# 5v_power_supply.net
KiCad netlist of a schematic drawn in EAGLE
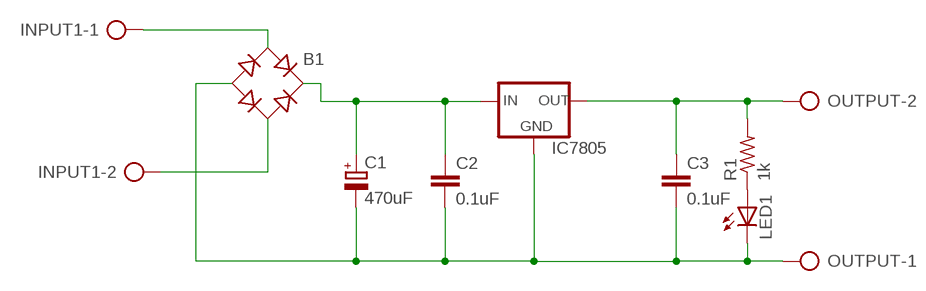
[diagram p0: schematic, sheet 1]

(export (version "E")
  (design (tool "Eeschema 10.0.6"))
  (components
    (comp (ref "B1")
      (value "RB1A")
      (footprint "eagle-import:RB1A")
      (libsource (lib "eagle-import") (part "RB1A"))
    )
    (comp (ref "C1")
      (value "470uF")
      (footprint "eagle-import:B45181B")
      (libsource (lib "eagle-import") (part "CPOL-EUB45181B"))
    )
    (comp (ref "C2")
      (value "0.1uF")
      (footprint "eagle-import:C050-025X075")
      (libsource (lib "eagle-import") (part "C-EU050-025X075"))
    )
    (comp (ref "C3")
      (value "0.1uF")
      (footprint "eagle-import:C050-025X075")
      (libsource (lib "eagle-import") (part "C-EU050-025X075"))
    )
    (comp (ref "IC7805")
      (value "78XXS")
      (footprint "eagle-import:78XXS")
      (libsource (lib "eagle-import") (part "78XXS"))
    )
    (comp (ref "INPUT1")
      (value "AK500/2-H")
      (footprint "eagle-import:AK500_2-H")
      (libsource (lib "eagle-import") (part "AK500/2-H"))
    )
    (comp (ref "LED1")
      (value "LED5MM")
      (footprint "eagle-import:LED5MM")
      (libsource (lib "eagle-import") (part "LED5MM"))
    )
    (comp (ref "OUTPUT")
      (value "AK500/2-H")
      (footprint "eagle-import:AK500_2-H")
      (libsource (lib "eagle-import") (part "AK500/2-H"))
    )
    (comp (ref "R1")
      (value "1k")
      (footprint "eagle-import:0207_10")
      (libsource (lib "eagle-import") (part "R-US_0207/10"))
    )
  )
  (nets
    (net (code "1") (name "Net-(B1-Pad+)") (class "Default")
      (node (ref "B1") (pin "+") (pinfunction "+_+") (pintype "passive"))
      (node (ref "C1") (pin "+") (pinfunction "+_+") (pintype "passive"))
      (node (ref "C2") (pin "1") (pinfunction "1_1") (pintype "passive"))
      (node (ref "IC7805") (pin "IN") (pinfunction "IN_IN") (pintype "input"))
    )
    (net (code "2") (name "Net-(INPUT1A-KL)") (class "Default")
      (node (ref "B1") (pin "AC1") (pinfunction "AC1_AC1") (pintype "passive"))
      (node (ref "INPUT1") (pin "1") (pinfunction "KL_1") (pintype "passive"))
    )
    (net (code "3") (name "Net-(INPUT1B-KL)") (class "Default")
      (node (ref "B1") (pin "AC2") (pinfunction "AC2_AC2") (pintype "passive"))
      (node (ref "INPUT1") (pin "2") (pinfunction "KL_2") (pintype "passive"))
    )
    (net (code "4") (name "Net-(LED1-C)") (class "Default")
      (node (ref "B1") (pin "-") (pinfunction "-_-") (pintype "passive"))
      (node (ref "C1") (pin "-") (pinfunction "-_-") (pintype "passive"))
      (node (ref "C2") (pin "2") (pinfunction "2_2") (pintype "passive"))
      (node (ref "C3") (pin "2") (pinfunction "2_2") (pintype "passive"))
      (node (ref "IC7805") (pin "GND") (pinfunction "GND_GND") (pintype "input"))
      (node (ref "LED1") (pin "K") (pinfunction "C_K") (pintype "passive"))
      (node (ref "OUTPUT") (pin "1") (pinfunction "KL_1") (pintype "passive"))
    )
    (net (code "5") (name "Net-(LED1-PadA)") (class "Default")
      (node (ref "LED1") (pin "A") (pinfunction "A_A") (pintype "passive"))
      (node (ref "R1") (pin "1") (pinfunction "1_1") (pintype "passive"))
    )
    (net (code "6") (name "Net-(OUTPUTB-KL)") (class "Default")
      (node (ref "C3") (pin "1") (pinfunction "1_1") (pintype "passive"))
      (node (ref "IC7805") (pin "OUT") (pinfunction "OUT_OUT") (pintype "passive"))
      (node (ref "OUTPUT") (pin "2") (pinfunction "KL_2") (pintype "passive"))
      (node (ref "R1") (pin "2") (pinfunction "2_2") (pintype "passive"))
    )
  )
)
